# schemat.net
KiCad netlist of a schematic drawn in EAGLE
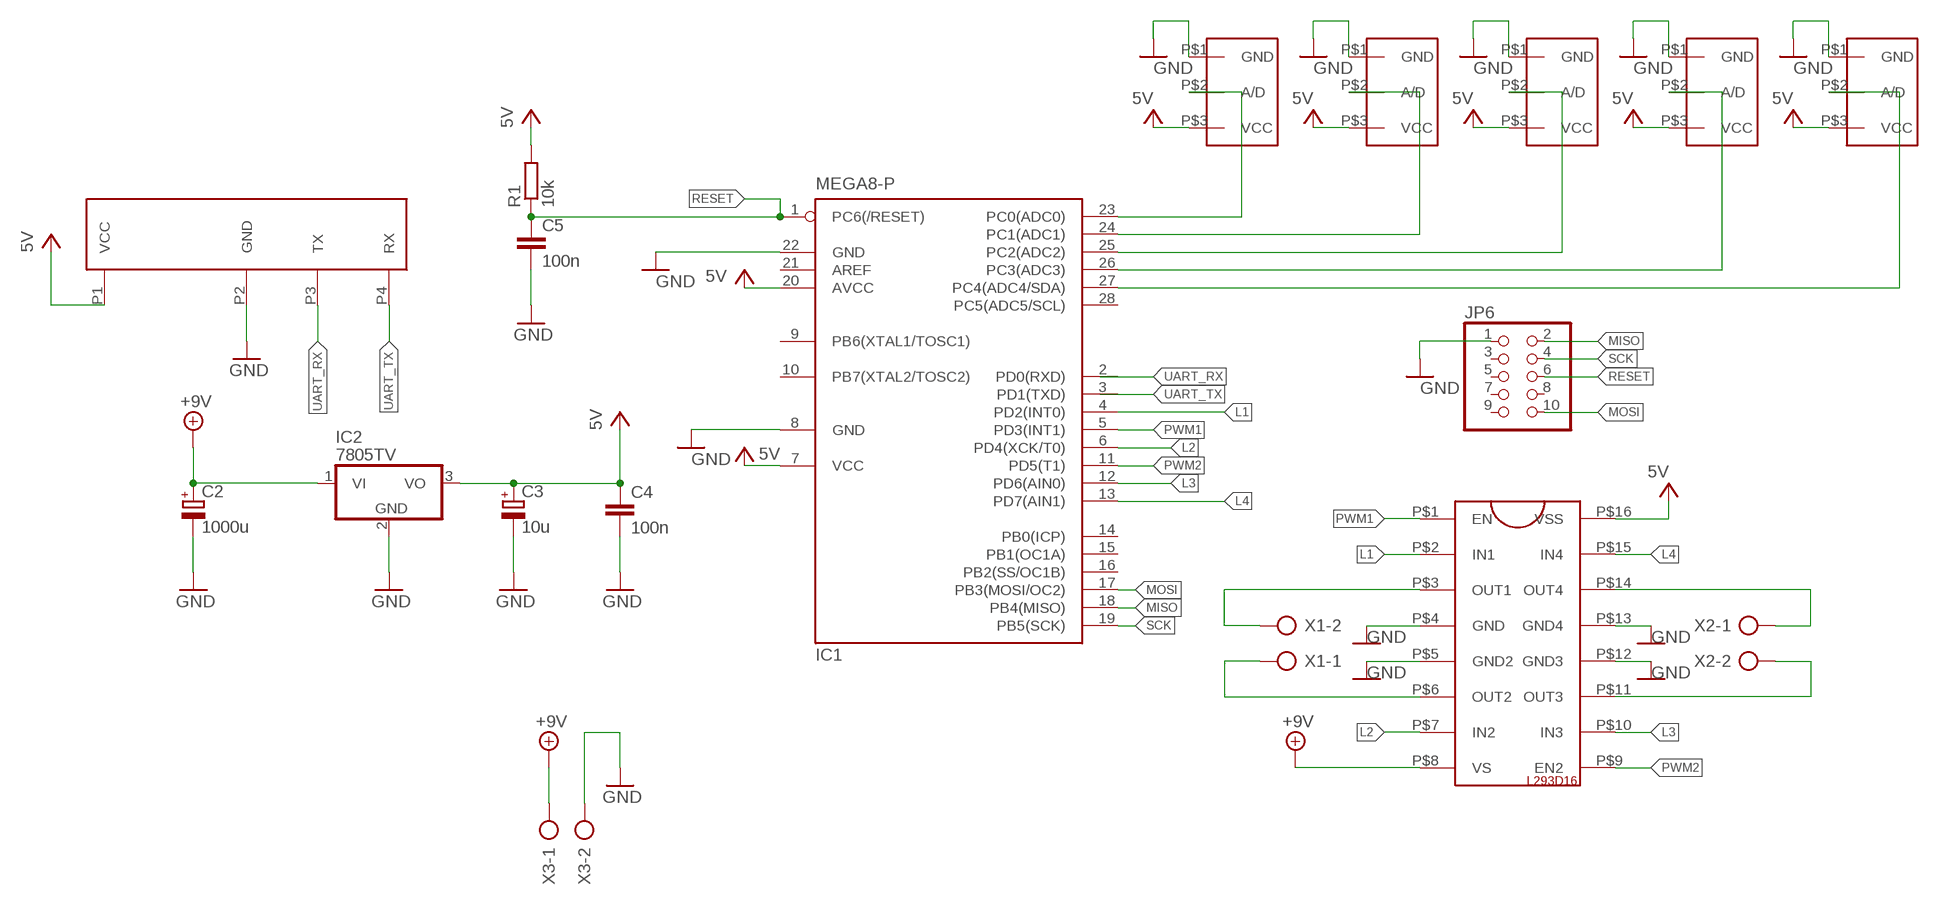
[diagram p0: schematic, sheet 1]

(export (version "E")
  (design (tool "Eeschema 10.0.6"))
  (components
    (comp (ref "C2")
      (value "1000u")
      (footprint "eagle-import:E5-10,5")
      (libsource (lib "eagle-import") (part "CPOL-EUE5-10.5"))
    )
    (comp (ref "C3")
      (value "10u")
      (footprint "eagle-import:E5-10,5")
      (libsource (lib "eagle-import") (part "CPOL-EUE5-10.5"))
    )
    (comp (ref "C4")
      (value "100n")
      (footprint "eagle-import:C050-075X075")
      (libsource (lib "eagle-import") (part "C-EU050-075X075"))
    )
    (comp (ref "C5")
      (value "100n")
      (footprint "eagle-import:C050-075X075")
      (libsource (lib "eagle-import") (part "C-EU050-075X075"))
    )
    (comp (ref "IC1")
      (value "MEGA8-P")
      (footprint "eagle-import:DIL28-3")
      (libsource (lib "eagle-import") (part "MEGA8-P"))
    )
    (comp (ref "IC2")
      (value "7805TV")
      (footprint "eagle-import:TO220V")
      (libsource (lib "eagle-import") (part "78TV05"))
    )
    (comp (ref "JP6")
      (value "PINHD-2X5")
      (footprint "eagle-import:2X05")
      (libsource (lib "eagle-import") (part "PINHD-2X5"))
    )
    (comp (ref "R1")
      (value "10k")
      (footprint "eagle-import:0309_10")
      (libsource (lib "eagle-import") (part "R-EU_0309/10"))
    )
    (comp (ref "TCRT1")
      (value "TCRT5000")
      (footprint "eagle-import:TCRT5000")
      (libsource (lib "eagle-import") (part "TCRT5000"))
    )
    (comp (ref "TCRT2")
      (value "TCRT5000")
      (footprint "eagle-import:TCRT5000")
      (libsource (lib "eagle-import") (part "TCRT5000"))
    )
    (comp (ref "TCRT6")
      (value "TCRT5000")
      (footprint "eagle-import:TCRT5000")
      (libsource (lib "eagle-import") (part "TCRT5000"))
    )
    (comp (ref "TCRT7")
      (value "TCRT5000")
      (footprint "eagle-import:TCRT5000")
      (libsource (lib "eagle-import") (part "TCRT5000"))
    )
    (comp (ref "TCRT8")
      (value "TCRT5000")
      (footprint "eagle-import:TCRT5000")
      (libsource (lib "eagle-import") (part "TCRT5000"))
    )
    (comp (ref "U$1")
      (value "BTM222BTM222")
      (footprint "eagle-import:BTM222")
      (libsource (lib "eagle-import") (part "BTM222BTM222"))
    )
    (comp (ref "U$2")
      (value "L293D16L293D16")
      (footprint "eagle-import:L293D")
      (libsource (lib "eagle-import") (part "L293D16L293D16"))
    )
    (comp (ref "X1")
      (value "AK500/2")
      (footprint "eagle-import:AK500_2")
      (libsource (lib "eagle-import") (part "AK500/2"))
    )
    (comp (ref "X2")
      (value "AK500/2")
      (footprint "eagle-import:AK500_2")
      (libsource (lib "eagle-import") (part "AK500/2"))
    )
    (comp (ref "X3")
      (value "AK500/2")
      (footprint "eagle-import:AK500_2")
      (libsource (lib "eagle-import") (part "AK500/2"))
    )
  )
  (nets
    (net (code "1") (name "+9V") (class "Default")
      (node (ref "C2") (pin "+") (pinfunction "+_+") (pintype "passive"))
      (node (ref "IC2") (pin "1") (pinfunction "VI_1") (pintype "input"))
      (node (ref "U$2") (pin "P$8") (pinfunction "VS_P$8") (pintype "bidirectional"))
      (node (ref "X3") (pin "1") (pinfunction "KL_1") (pintype "passive"))
    )
    (net (code "2") (name "5V") (class "Default")
      (node (ref "C3") (pin "+") (pinfunction "+_+") (pintype "passive"))
      (node (ref "C4") (pin "1") (pinfunction "1_1") (pintype "passive"))
      (node (ref "IC1") (pin "20") (pinfunction "AVCC_20") (pintype "power_in"))
      (node (ref "IC1") (pin "7") (pinfunction "VCC_7") (pintype "power_in"))
      (node (ref "IC2") (pin "3") (pinfunction "VO_3") (pintype "passive"))
      (node (ref "R1") (pin "2") (pinfunction "2_2") (pintype "passive"))
      (node (ref "TCRT1") (pin "P$3") (pinfunction "VCC_P$3") (pintype "bidirectional"))
      (node (ref "TCRT2") (pin "P$3") (pinfunction "VCC_P$3") (pintype "bidirectional"))
      (node (ref "TCRT6") (pin "P$3") (pinfunction "VCC_P$3") (pintype "bidirectional"))
      (node (ref "TCRT7") (pin "P$3") (pinfunction "VCC_P$3") (pintype "bidirectional"))
      (node (ref "TCRT8") (pin "P$3") (pinfunction "VCC_P$3") (pintype "bidirectional"))
      (node (ref "U$1") (pin "P1") (pinfunction "VCC_P1") (pintype "bidirectional"))
      (node (ref "U$2") (pin "P$16") (pinfunction "VSS_P$16") (pintype "bidirectional"))
    )
    (net (code "3") (name "GND") (class "Default")
      (node (ref "C2") (pin "-") (pinfunction "-_-") (pintype "passive"))
      (node (ref "C3") (pin "-") (pinfunction "-_-") (pintype "passive"))
      (node (ref "C4") (pin "2") (pinfunction "2_2") (pintype "passive"))
      (node (ref "C5") (pin "2") (pinfunction "2_2") (pintype "passive"))
      (node (ref "IC1") (pin "22") (pinfunction "GND_22") (pintype "power_in"))
      (node (ref "IC1") (pin "8") (pinfunction "GND_8") (pintype "power_in"))
      (node (ref "IC2") (pin "2") (pinfunction "GND_2") (pintype "passive"))
      (node (ref "JP6") (pin "1") (pinfunction "1_1") (pintype "passive"))
      (node (ref "TCRT1") (pin "P$1") (pinfunction "GND_P$1") (pintype "bidirectional"))
      (node (ref "TCRT2") (pin "P$1") (pinfunction "GND_P$1") (pintype "bidirectional"))
      (node (ref "TCRT6") (pin "P$1") (pinfunction "GND_P$1") (pintype "bidirectional"))
      (node (ref "TCRT7") (pin "P$1") (pinfunction "GND_P$1") (pintype "bidirectional"))
      (node (ref "TCRT8") (pin "P$1") (pinfunction "GND_P$1") (pintype "bidirectional"))
      (node (ref "U$1") (pin "P2") (pinfunction "GND_P2") (pintype "bidirectional"))
      (node (ref "U$2") (pin "P$12") (pinfunction "GND3_P$12") (pintype "bidirectional"))
      (node (ref "U$2") (pin "P$13") (pinfunction "GND4_P$13") (pintype "bidirectional"))
      (node (ref "U$2") (pin "P$4") (pinfunction "GND_P$4") (pintype "bidirectional"))
      (node (ref "U$2") (pin "P$5") (pinfunction "GND2_P$5") (pintype "bidirectional"))
      (node (ref "X3") (pin "2") (pinfunction "KL_2") (pintype "passive"))
    )
    (net (code "4") (name "L1") (class "Default")
      (node (ref "IC1") (pin "4") (pinfunction "PD2(INT0)_4") (pintype "bidirectional"))
      (node (ref "U$2") (pin "P$2") (pinfunction "IN1_P$2") (pintype "bidirectional"))
    )
    (net (code "5") (name "L2") (class "Default")
      (node (ref "IC1") (pin "6") (pinfunction "PD4(XCK/T0)_6") (pintype "bidirectional"))
      (node (ref "U$2") (pin "P$7") (pinfunction "IN2_P$7") (pintype "bidirectional"))
    )
    (net (code "6") (name "L3") (class "Default")
      (node (ref "IC1") (pin "12") (pinfunction "PD6(AIN0)_12") (pintype "bidirectional"))
      (node (ref "U$2") (pin "P$10") (pinfunction "IN3_P$10") (pintype "bidirectional"))
    )
    (net (code "7") (name "L4") (class "Default")
      (node (ref "IC1") (pin "13") (pinfunction "PD7(AIN1)_13") (pintype "bidirectional"))
      (node (ref "U$2") (pin "P$15") (pinfunction "IN4_P$15") (pintype "bidirectional"))
    )
    (net (code "8") (name "MISO") (class "Default")
      (node (ref "IC1") (pin "18") (pinfunction "PB4(MISO)_18") (pintype "bidirectional"))
      (node (ref "JP6") (pin "2") (pinfunction "2_2") (pintype "passive"))
    )
    (net (code "9") (name "MOSI") (class "Default")
      (node (ref "IC1") (pin "17") (pinfunction "PB3(MOSI/OC2)_17") (pintype "bidirectional"))
      (node (ref "JP6") (pin "10") (pinfunction "10_10") (pintype "passive"))
    )
    (net (code "10") (name "Net-(IC1-PC0(ADC0))") (class "Default")
      (node (ref "IC1") (pin "23") (pinfunction "PC0(ADC0)_23") (pintype "bidirectional"))
      (node (ref "TCRT2") (pin "P$2") (pinfunction "A/D_P$2") (pintype "bidirectional"))
    )
    (net (code "11") (name "Net-(IC1-PC1(ADC1))") (class "Default")
      (node (ref "IC1") (pin "24") (pinfunction "PC1(ADC1)_24") (pintype "bidirectional"))
      (node (ref "TCRT1") (pin "P$2") (pinfunction "A/D_P$2") (pintype "bidirectional"))
    )
    (net (code "12") (name "Net-(IC1-PC2(ADC2))") (class "Default")
      (node (ref "IC1") (pin "25") (pinfunction "PC2(ADC2)_25") (pintype "bidirectional"))
      (node (ref "TCRT8") (pin "P$2") (pinfunction "A/D_P$2") (pintype "bidirectional"))
    )
    (net (code "13") (name "Net-(IC1-PC3(ADC3))") (class "Default")
      (node (ref "IC1") (pin "26") (pinfunction "PC3(ADC3)_26") (pintype "bidirectional"))
      (node (ref "TCRT7") (pin "P$2") (pinfunction "A/D_P$2") (pintype "bidirectional"))
    )
    (net (code "14") (name "Net-(IC1-PC4(ADC4{slash}SDA))") (class "Default")
      (node (ref "IC1") (pin "27") (pinfunction "PC4(ADC4/SDA)_27") (pintype "bidirectional"))
      (node (ref "TCRT6") (pin "P$2") (pinfunction "A/D_P$2") (pintype "bidirectional"))
    )
    (net (code "15") (name "Net-(U$2-OUT1)") (class "Default")
      (node (ref "U$2") (pin "P$3") (pinfunction "OUT1_P$3") (pintype "bidirectional"))
      (node (ref "X1") (pin "2") (pinfunction "KL_2") (pintype "passive"))
    )
    (net (code "16") (name "Net-(U$2-OUT2)") (class "Default")
      (node (ref "U$2") (pin "P$6") (pinfunction "OUT2_P$6") (pintype "bidirectional"))
      (node (ref "X1") (pin "1") (pinfunction "KL_1") (pintype "passive"))
    )
    (net (code "17") (name "Net-(U$2-OUT3)") (class "Default")
      (node (ref "U$2") (pin "P$11") (pinfunction "OUT3_P$11") (pintype "bidirectional"))
      (node (ref "X2") (pin "2") (pinfunction "KL_2") (pintype "passive"))
    )
    (net (code "18") (name "Net-(U$2-OUT4)") (class "Default")
      (node (ref "U$2") (pin "P$14") (pinfunction "OUT4_P$14") (pintype "bidirectional"))
      (node (ref "X2") (pin "1") (pinfunction "KL_1") (pintype "passive"))
    )
    (net (code "19") (name "PWM1") (class "Default")
      (node (ref "IC1") (pin "5") (pinfunction "PD3(INT1)_5") (pintype "bidirectional"))
      (node (ref "U$2") (pin "P$1") (pinfunction "EN_P$1") (pintype "bidirectional"))
    )
    (net (code "20") (name "PWM2") (class "Default")
      (node (ref "IC1") (pin "11") (pinfunction "PD5(T1)_11") (pintype "bidirectional"))
      (node (ref "U$2") (pin "P$9") (pinfunction "EN2_P$9") (pintype "bidirectional"))
    )
    (net (code "21") (name "RESET") (class "Default")
      (node (ref "C5") (pin "1") (pinfunction "1_1") (pintype "passive"))
      (node (ref "IC1") (pin "1") (pinfunction "PC6(/RESET)_1") (pintype "bidirectional"))
      (node (ref "JP6") (pin "6") (pinfunction "6_6") (pintype "passive"))
      (node (ref "R1") (pin "1") (pinfunction "1_1") (pintype "passive"))
    )
    (net (code "22") (name "SCK") (class "Default")
      (node (ref "IC1") (pin "19") (pinfunction "PB5(SCK)_19") (pintype "bidirectional"))
      (node (ref "JP6") (pin "4") (pinfunction "4_4") (pintype "passive"))
    )
    (net (code "23") (name "UART_RX") (class "Default")
      (node (ref "IC1") (pin "2") (pinfunction "PD0(RXD)_2") (pintype "bidirectional"))
      (node (ref "U$1") (pin "P3") (pinfunction "TX_P3") (pintype "bidirectional"))
    )
    (net (code "24") (name "UART_TX") (class "Default")
      (node (ref "IC1") (pin "3") (pinfunction "PD1(TXD)_3") (pintype "bidirectional"))
      (node (ref "U$1") (pin "P4") (pinfunction "RX_P4") (pintype "bidirectional"))
    )
    (net (code "25") (name "unconnected-(IC1-AREF-Pad21)") (class "Default")
      (node (ref "IC1") (pin "21") (pinfunction "AREF_21") (pintype "passive"))
    )
    (net (code "26") (name "unconnected-(IC1-PB0(ICP)-Pad14)") (class "Default")
      (node (ref "IC1") (pin "14") (pinfunction "PB0(ICP)_14") (pintype "bidirectional"))
    )
    (net (code "27") (name "unconnected-(IC1-PB1(OC1A)-Pad15)") (class "Default")
      (node (ref "IC1") (pin "15") (pinfunction "PB1(OC1A)_15") (pintype "bidirectional"))
    )
    (net (code "28") (name "unconnected-(IC1-PB2(SS{slash}OC1B)-Pad16)") (class "Default")
      (node (ref "IC1") (pin "16") (pinfunction "PB2(SS/OC1B)_16") (pintype "bidirectional"))
    )
    (net (code "29") (name "unconnected-(IC1-PB6(XTAL1{slash}TOSC1)-Pad9)") (class "Default")
      (node (ref "IC1") (pin "9") (pinfunction "PB6(XTAL1/TOSC1)_9") (pintype "bidirectional"))
    )
    (net (code "30") (name "unconnected-(IC1-PB7(XTAL2{slash}TOSC2)-Pad10)") (class "Default")
      (node (ref "IC1") (pin "10") (pinfunction "PB7(XTAL2/TOSC2)_10") (pintype "bidirectional"))
    )
    (net (code "31") (name "unconnected-(IC1-PC5(ADC5{slash}SCL)-Pad28)") (class "Default")
      (node (ref "IC1") (pin "28") (pinfunction "PC5(ADC5/SCL)_28") (pintype "bidirectional"))
    )
    (net (code "32") (name "unconnected-(JP6-Pad3)") (class "Default")
      (node (ref "JP6") (pin "3") (pinfunction "3_3") (pintype "passive"))
    )
    (net (code "33") (name "unconnected-(JP6-Pad5)") (class "Default")
      (node (ref "JP6") (pin "5") (pinfunction "5_5") (pintype "passive"))
    )
    (net (code "34") (name "unconnected-(JP6-Pad7)") (class "Default")
      (node (ref "JP6") (pin "7") (pinfunction "7_7") (pintype "passive"))
    )
    (net (code "35") (name "unconnected-(JP6-Pad8)") (class "Default")
      (node (ref "JP6") (pin "8") (pinfunction "8_8") (pintype "passive"))
    )
    (net (code "36") (name "unconnected-(JP6-Pad9)") (class "Default")
      (node (ref "JP6") (pin "9") (pinfunction "9_9") (pintype "passive"))
    )
  )
)
